# base-base.net
KiCad netlist of a schematic drawn in EAGLE
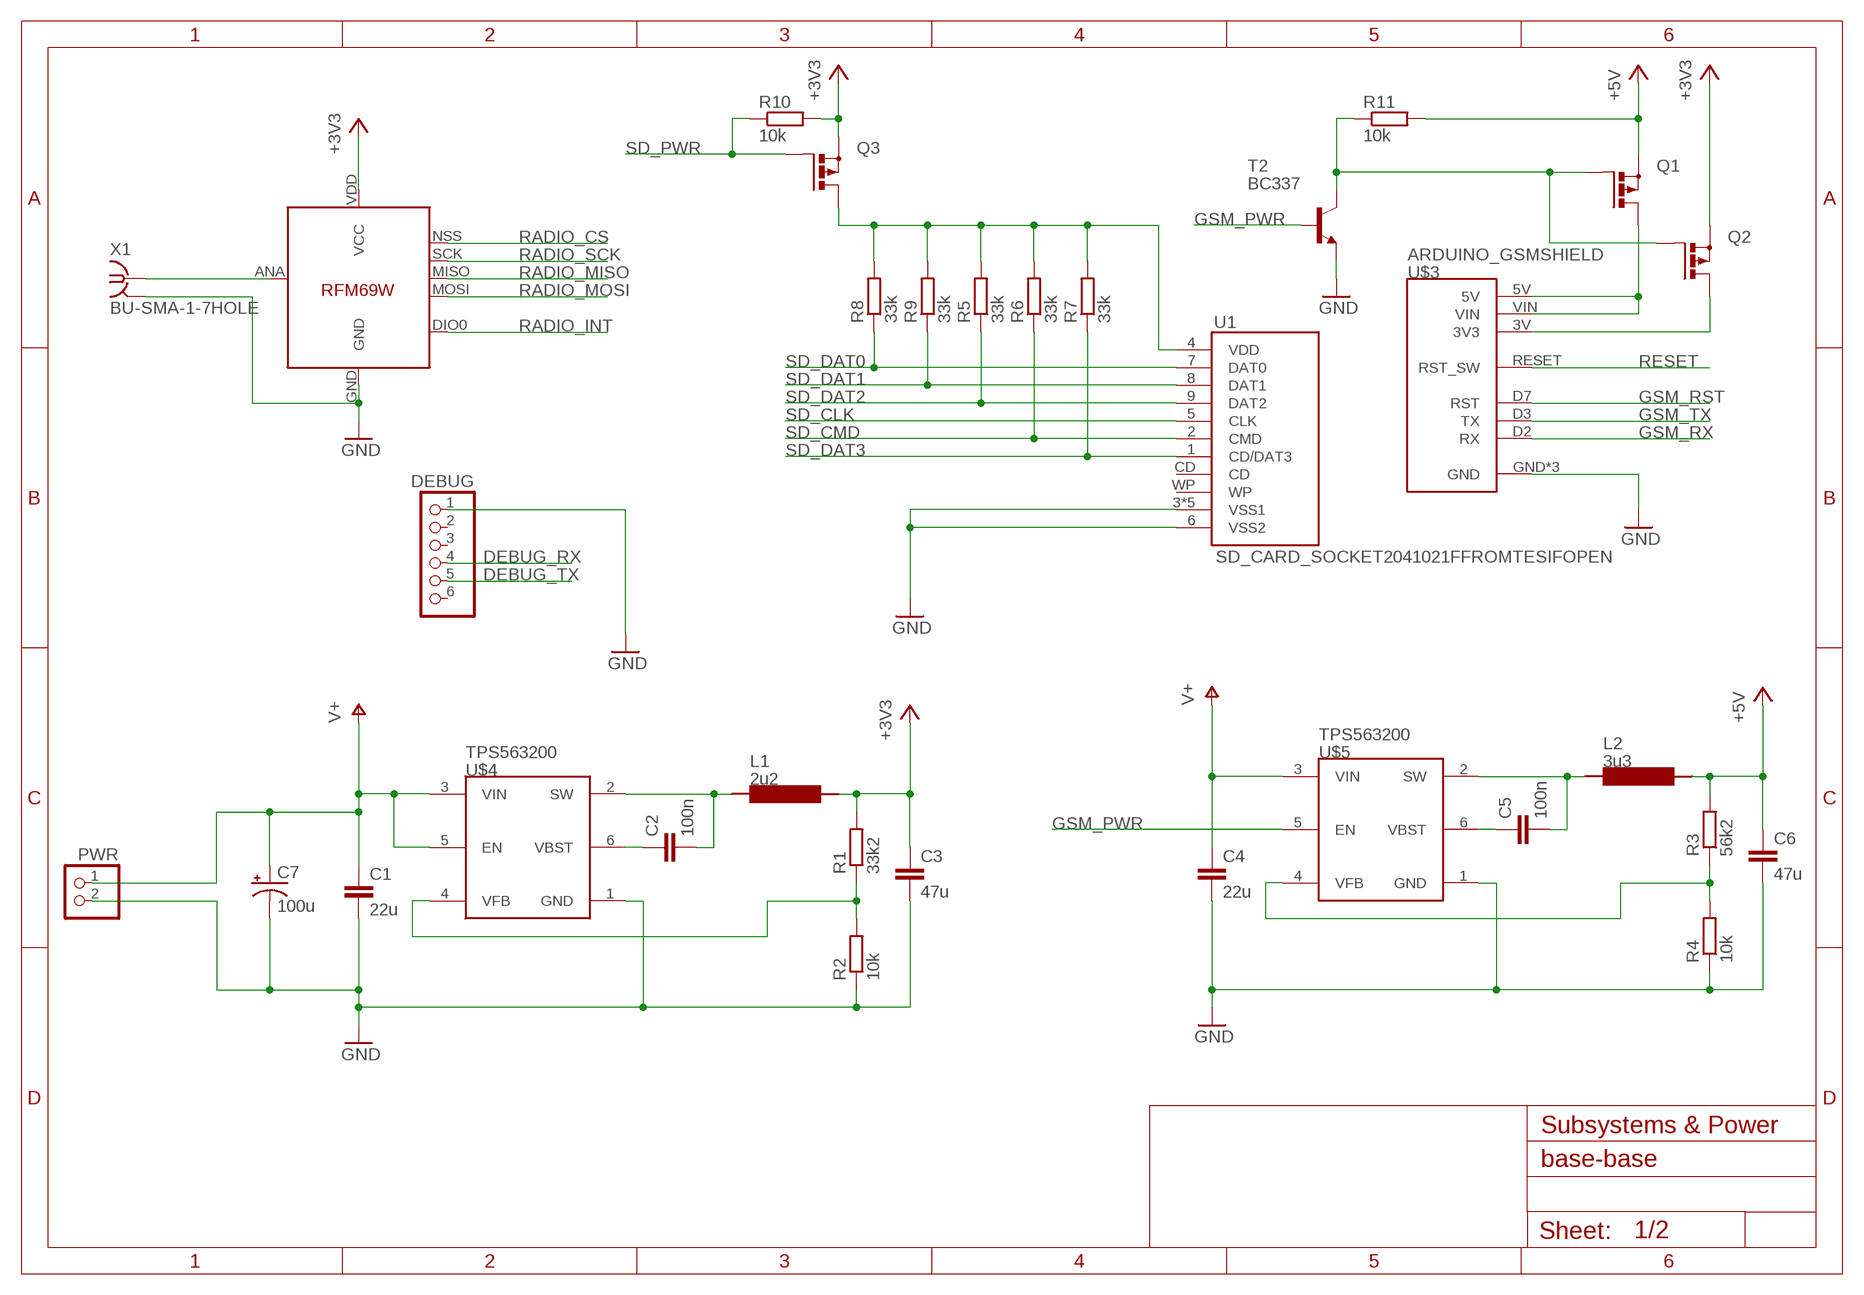
[diagram p0: schematic, sheet 1]
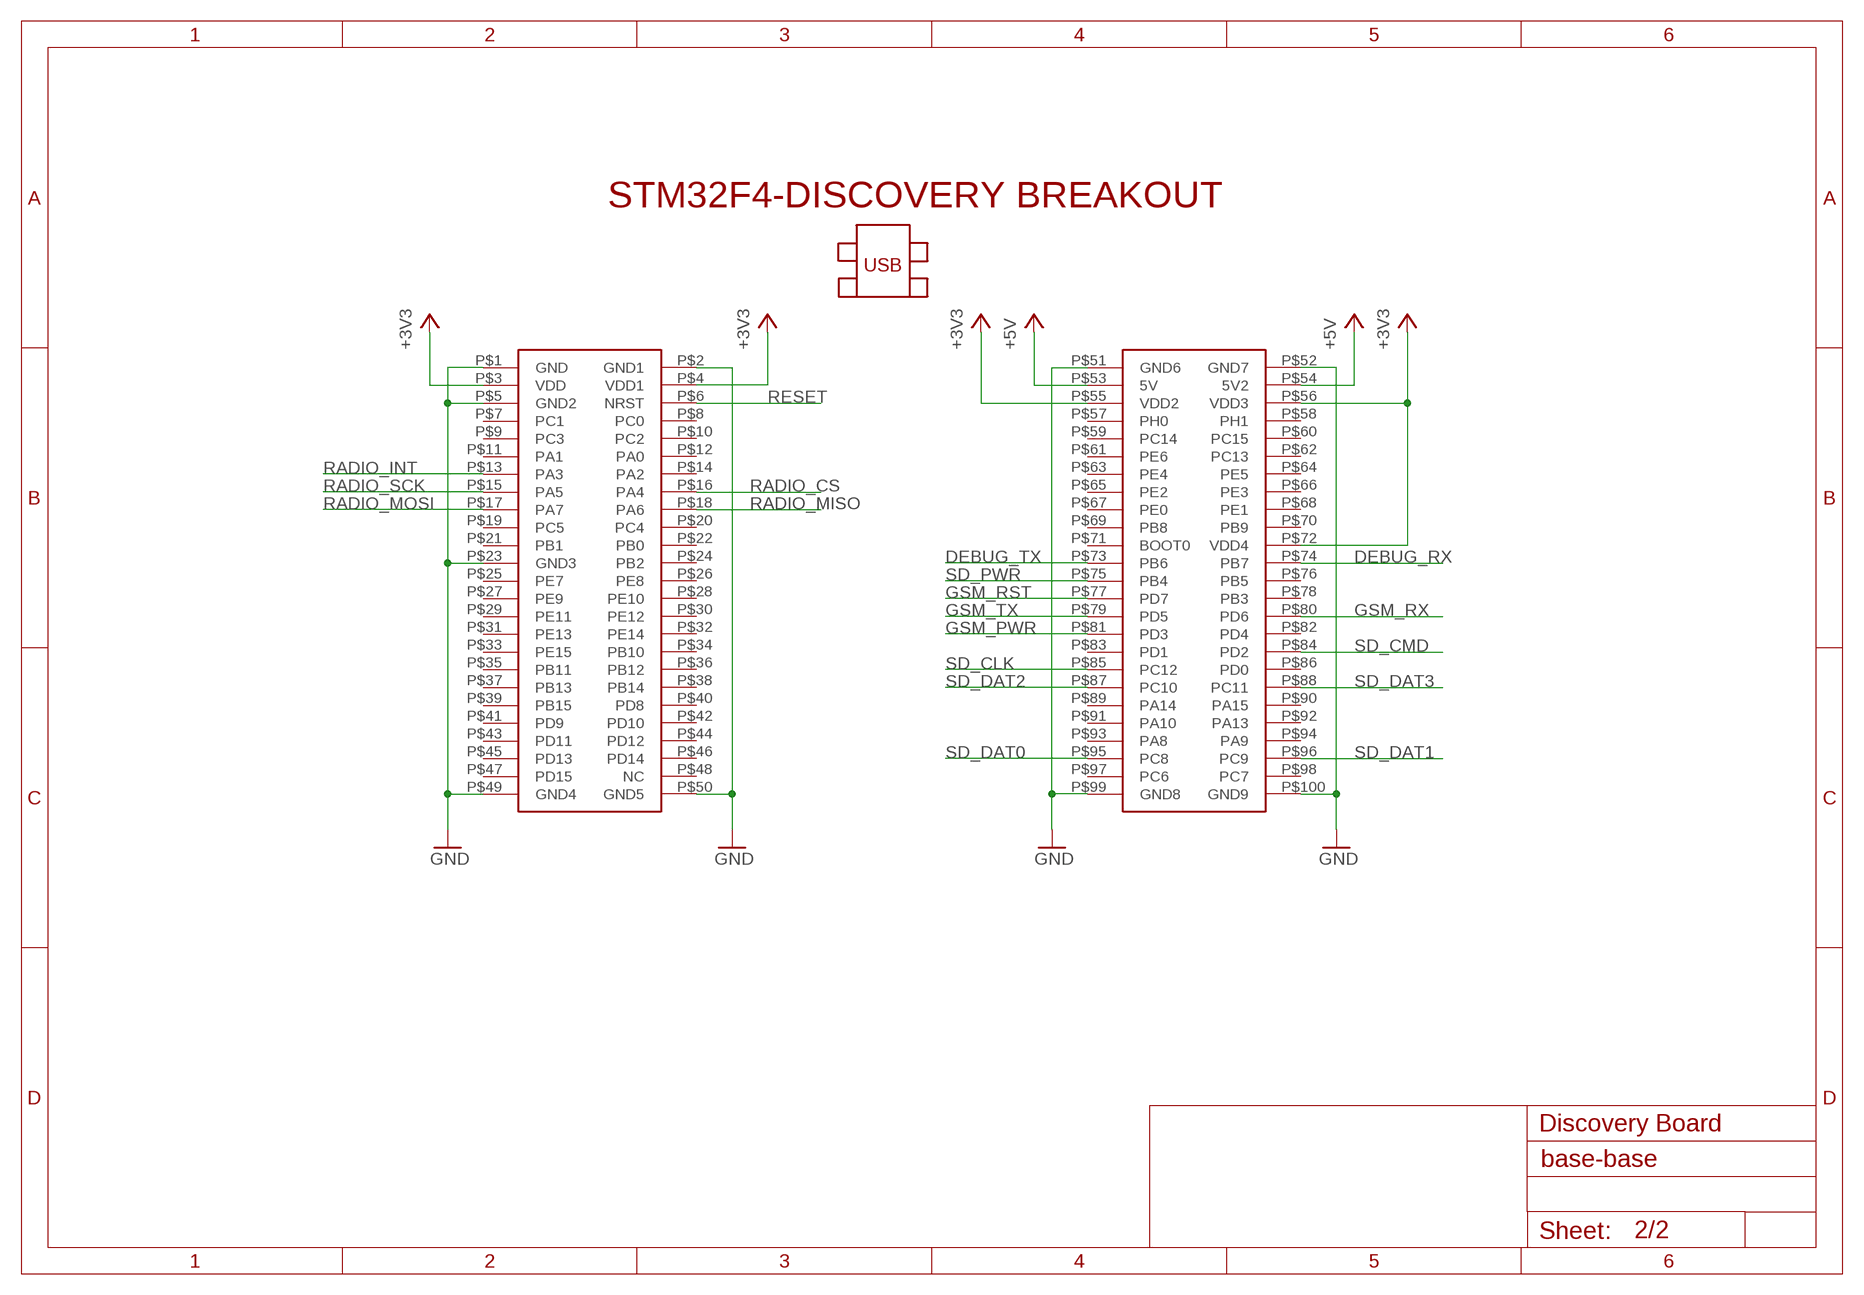
[diagram p1: schematic, sheet 2]

(export (version "E")
  (design (tool "Eeschema 10.0.6"))
  (components
    (comp (ref "U$1")
      (value "STM32F4-DISCOVERY")
      (footprint "eagle-import:STM32F4-DISCOVERY")
      (libsource (lib "eagle-import") (part "STM32F4-DISCOVERY"))
    )
    (comp (ref "C1")
      (value "22u")
      (footprint "eagle-import:1206")
      (libsource (lib "eagle-import") (part "CAP1206"))
    )
    (comp (ref "C2")
      (value "100n")
      (footprint "eagle-import:CAP-PTH-SMALL")
      (libsource (lib "eagle-import") (part "CAPPTH"))
    )
    (comp (ref "C3")
      (value "47u")
      (footprint "eagle-import:1206")
      (libsource (lib "eagle-import") (part "CAP1206"))
    )
    (comp (ref "C4")
      (value "22u")
      (footprint "eagle-import:1206")
      (libsource (lib "eagle-import") (part "CAP1206"))
    )
    (comp (ref "C5")
      (value "100n")
      (footprint "eagle-import:CAP-PTH-SMALL")
      (libsource (lib "eagle-import") (part "CAPPTH"))
    )
    (comp (ref "C6")
      (value "47u")
      (footprint "eagle-import:1206")
      (libsource (lib "eagle-import") (part "CAP1206"))
    )
    (comp (ref "C7")
      (value "100u")
      (footprint "eagle-import:CPOL-RADIAL-10UF-25V")
      (libsource (lib "eagle-import") (part "CAP_POLPTH2"))
    )
    (comp (ref "DEBUG")
      (value "PINHD-1X6")
      (footprint "eagle-import:1X06")
      (libsource (lib "eagle-import") (part "PINHD-1X6"))
    )
    (comp (ref "L1")
      (value "2u2")
      (footprint "eagle-import:SRR7032")
      (libsource (lib "eagle-import") (part "SRR7032"))
    )
    (comp (ref "L2")
      (value "3u3")
      (footprint "eagle-import:SRR7032")
      (libsource (lib "eagle-import") (part "SRR7032"))
    )
    (comp (ref "PWR")
      (value "PINHD-1X2")
      (footprint "eagle-import:1X02")
      (libsource (lib "eagle-import") (part "PINHD-1X2"))
    )
    (comp (ref "Q1")
      (value "PMOSFET_PTO220BH")
      (footprint "eagle-import:TO220BH")
      (libsource (lib "eagle-import") (part "PMOSFET_PTO220BH"))
    )
    (comp (ref "Q2")
      (value "PMOSFET_PTO220BH")
      (footprint "eagle-import:TO220BH")
      (libsource (lib "eagle-import") (part "PMOSFET_PTO220BH"))
    )
    (comp (ref "Q3")
      (value "PMOSFET_PTO220BH")
      (footprint "eagle-import:TO220BH")
      (libsource (lib "eagle-import") (part "PMOSFET_PTO220BH"))
    )
    (comp (ref "R1")
      (value "33k2")
      (footprint "eagle-import:0204_7")
      (libsource (lib "eagle-import") (part "R-EU_0204/7"))
    )
    (comp (ref "R2")
      (value "10k")
      (footprint "eagle-import:0204_7")
      (libsource (lib "eagle-import") (part "R-EU_0204/7"))
    )
    (comp (ref "R3")
      (value "56k2")
      (footprint "eagle-import:0204_7")
      (libsource (lib "eagle-import") (part "R-EU_0204/7"))
    )
    (comp (ref "R4")
      (value "10k")
      (footprint "eagle-import:0204_7")
      (libsource (lib "eagle-import") (part "R-EU_0204/7"))
    )
    (comp (ref "R5")
      (value "33k")
      (footprint "eagle-import:0204_7")
      (libsource (lib "eagle-import") (part "R-EU_0204/7"))
    )
    (comp (ref "R6")
      (value "33k")
      (footprint "eagle-import:0204_7")
      (libsource (lib "eagle-import") (part "R-EU_0204/7"))
    )
    (comp (ref "R7")
      (value "33k")
      (footprint "eagle-import:0204_7")
      (libsource (lib "eagle-import") (part "R-EU_0204/7"))
    )
    (comp (ref "R8")
      (value "33k")
      (footprint "eagle-import:0204_7")
      (libsource (lib "eagle-import") (part "R-EU_0204/7"))
    )
    (comp (ref "R9")
      (value "33k")
      (footprint "eagle-import:0204_7")
      (libsource (lib "eagle-import") (part "R-EU_0204/7"))
    )
    (comp (ref "R10")
      (value "10k")
      (footprint "eagle-import:0204_7")
      (libsource (lib "eagle-import") (part "R-EU_0204/7"))
    )
    (comp (ref "R11")
      (value "10k")
      (footprint "eagle-import:0204_7")
      (libsource (lib "eagle-import") (part "R-EU_0204/7"))
    )
    (comp (ref "T2")
      (value "BC337")
      (footprint "eagle-import:TO92")
      (libsource (lib "eagle-import") (part "BC337"))
    )
    (comp (ref "U$2")
      (value "RFM69")
      (footprint "eagle-import:RFM69W-MINPADS")
      (libsource (lib "eagle-import") (part "RFM69"))
    )
    (comp (ref "U$3")
      (value "ARDUINO_GSMSHIELD")
      (footprint "eagle-import:ARDUINO-NOHOLE")
      (libsource (lib "eagle-import") (part "ARDUINO_GSMSHIELD"))
    )
    (comp (ref "U$4")
      (value "TPS563200")
      (footprint "eagle-import:DDC0006A")
      (libsource (lib "eagle-import") (part "TPS563200"))
    )
    (comp (ref "U$5")
      (value "TPS563200")
      (footprint "eagle-import:DDC0006A")
      (libsource (lib "eagle-import") (part "TPS563200"))
    )
    (comp (ref "U1")
      (value "SD_CARD_SOCKET2041021FFROMTESIFOPEN")
      (footprint "eagle-import:SDCARD_2041021-3")
      (libsource (lib "eagle-import") (part "SD_CARD_SOCKET2041021FFROMTESIFOPEN"))
    )
    (comp (ref "X1")
      (value "BU-SMA-1-7HOLE")
      (footprint "eagle-import:SMA_1-7HOLES")
      (libsource (lib "eagle-import") (part "BU-SMA-1-7HOLE"))
    )
  )
  (nets
    (net (code "1") (name "+3V3") (class "Default")
      (node (ref "C3") (pin "1") (pinfunction "1_1") (pintype "passive"))
      (node (ref "L1") (pin "2") (pinfunction "2_2") (pintype "passive"))
      (node (ref "Q2") (pin "S") (pinfunction "S_S") (pintype "passive"))
      (node (ref "Q3") (pin "S") (pinfunction "S_S") (pintype "passive"))
      (node (ref "R1") (pin "2") (pinfunction "2_2") (pintype "passive"))
      (node (ref "R10") (pin "2") (pinfunction "2_2") (pintype "passive"))
      (node (ref "U$1") (pin "P$3") (pinfunction "VDD_P$3") (pintype "bidirectional"))
      (node (ref "U$1") (pin "P$4") (pinfunction "VDD1_P$4") (pintype "bidirectional"))
      (node (ref "U$1") (pin "P$55") (pinfunction "VDD2_P$55") (pintype "bidirectional"))
      (node (ref "U$1") (pin "P$56") (pinfunction "VDD3_P$56") (pintype "bidirectional"))
      (node (ref "U$1") (pin "P$72") (pinfunction "VDD4_P$72") (pintype "bidirectional"))
      (node (ref "U$2") (pin "VDD") (pinfunction "VCC_VDD") (pintype "power_in"))
    )
    (net (code "2") (name "+5V") (class "Default")
      (node (ref "C6") (pin "1") (pinfunction "1_1") (pintype "passive"))
      (node (ref "L2") (pin "2") (pinfunction "2_2") (pintype "passive"))
      (node (ref "Q1") (pin "S") (pinfunction "S_S") (pintype "passive"))
      (node (ref "R11") (pin "2") (pinfunction "2_2") (pintype "passive"))
      (node (ref "R3") (pin "2") (pinfunction "2_2") (pintype "passive"))
      (node (ref "U$1") (pin "P$53") (pinfunction "5V_P$53") (pintype "bidirectional"))
      (node (ref "U$1") (pin "P$54") (pinfunction "5V2_P$54") (pintype "bidirectional"))
    )
    (net (code "3") (name "DEBUG_RX") (class "Default")
      (node (ref "DEBUG") (pin "4") (pinfunction "4_4") (pintype "passive"))
      (node (ref "U$1") (pin "P$74") (pinfunction "PB7_P$74") (pintype "bidirectional"))
    )
    (net (code "4") (name "DEBUG_TX") (class "Default")
      (node (ref "DEBUG") (pin "5") (pinfunction "5_5") (pintype "passive"))
      (node (ref "U$1") (pin "P$73") (pinfunction "PB6_P$73") (pintype "bidirectional"))
    )
    (net (code "5") (name "GND") (class "Default")
      (node (ref "C1") (pin "2") (pinfunction "2_2") (pintype "passive"))
      (node (ref "C3") (pin "2") (pinfunction "2_2") (pintype "passive"))
      (node (ref "C4") (pin "2") (pinfunction "2_2") (pintype "passive"))
      (node (ref "C6") (pin "2") (pinfunction "2_2") (pintype "passive"))
      (node (ref "C7") (pin "2") (pinfunction "-_2") (pintype "passive"))
      (node (ref "DEBUG") (pin "1") (pinfunction "1_1") (pintype "passive"))
      (node (ref "PWR") (pin "2") (pinfunction "2_2") (pintype "passive"))
      (node (ref "R2") (pin "1") (pinfunction "1_1") (pintype "passive"))
      (node (ref "R4") (pin "1") (pinfunction "1_1") (pintype "passive"))
      (node (ref "T2") (pin "1") (pinfunction "E_1") (pintype "passive"))
      (node (ref "U$1") (pin "P$1") (pinfunction "GND_P$1") (pintype "bidirectional"))
      (node (ref "U$1") (pin "P$100") (pinfunction "GND9_P$100") (pintype "bidirectional"))
      (node (ref "U$1") (pin "P$2") (pinfunction "GND1_P$2") (pintype "bidirectional"))
      (node (ref "U$1") (pin "P$23") (pinfunction "GND3_P$23") (pintype "bidirectional"))
      (node (ref "U$1") (pin "P$49") (pinfunction "GND4_P$49") (pintype "bidirectional"))
      (node (ref "U$1") (pin "P$5") (pinfunction "GND2_P$5") (pintype "bidirectional"))
      (node (ref "U$1") (pin "P$50") (pinfunction "GND5_P$50") (pintype "bidirectional"))
      (node (ref "U$1") (pin "P$51") (pinfunction "GND6_P$51") (pintype "bidirectional"))
      (node (ref "U$1") (pin "P$52") (pinfunction "GND7_P$52") (pintype "bidirectional"))
      (node (ref "U$1") (pin "P$99") (pinfunction "GND8_P$99") (pintype "bidirectional"))
      (node (ref "U$2") (pin "GND") (pinfunction "GND_GND") (pintype "power_in"))
      (node (ref "U$3") (pin "GND") (pinfunction "GND_GND") (pintype "bidirectional"))
      (node (ref "U$3") (pin "GND1") (pinfunction "GND_GND1") (pintype "bidirectional"))
      (node (ref "U$3") (pin "GND2") (pinfunction "GND_GND2") (pintype "bidirectional"))
      (node (ref "U$4") (pin "1") (pinfunction "GND_1") (pintype "bidirectional"))
      (node (ref "U$5") (pin "1") (pinfunction "GND_1") (pintype "bidirectional"))
      (node (ref "U1") (pin "3") (pinfunction "VSS1_3") (pintype "power_in"))
      (node (ref "U1") (pin "6") (pinfunction "VSS2_6") (pintype "power_in"))
      (node (ref "U1") (pin "SH1") (pinfunction "VSS1_SH1") (pintype "power_in"))
      (node (ref "U1") (pin "SH2") (pinfunction "VSS1_SH2") (pintype "power_in"))
      (node (ref "U1") (pin "SH3") (pinfunction "VSS1_SH3") (pintype "power_in"))
      (node (ref "U1") (pin "SH4") (pinfunction "VSS1_SH4") (pintype "power_in"))
      (node (ref "X1") (pin "2") (pinfunction "2_2") (pintype "passive"))
      (node (ref "X1") (pin "3") (pinfunction "2_3") (pintype "passive"))
      (node (ref "X1") (pin "4") (pinfunction "2_4") (pintype "passive"))
      (node (ref "X1") (pin "5") (pinfunction "2_5") (pintype "passive"))
    )
    (net (code "6") (name "GSM_PWR") (class "Default")
      (node (ref "T2") (pin "2") (pinfunction "B_2") (pintype "passive"))
      (node (ref "U$1") (pin "P$81") (pinfunction "PD3_P$81") (pintype "bidirectional"))
      (node (ref "U$5") (pin "5") (pinfunction "EN_5") (pintype "bidirectional"))
    )
    (net (code "7") (name "GSM_RST") (class "Default")
      (node (ref "U$1") (pin "P$77") (pinfunction "PD7_P$77") (pintype "bidirectional"))
      (node (ref "U$3") (pin "D7") (pinfunction "RST_D7") (pintype "bidirectional"))
    )
    (net (code "8") (name "GSM_RX") (class "Default")
      (node (ref "U$1") (pin "P$80") (pinfunction "PD6_P$80") (pintype "bidirectional"))
      (node (ref "U$3") (pin "D2") (pinfunction "RX_D2") (pintype "bidirectional"))
    )
    (net (code "9") (name "GSM_TX") (class "Default")
      (node (ref "U$1") (pin "P$79") (pinfunction "PD5_P$79") (pintype "bidirectional"))
      (node (ref "U$3") (pin "D3") (pinfunction "TX_D3") (pintype "bidirectional"))
    )
    (net (code "10") (name "Net-(Q1-PadD)") (class "Default")
      (node (ref "Q1") (pin "D") (pinfunction "D_D") (pintype "passive"))
      (node (ref "U$3") (pin "5V") (pinfunction "5V_5V") (pintype "bidirectional"))
      (node (ref "U$3") (pin "VIN") (pinfunction "VIN_VIN") (pintype "bidirectional"))
    )
    (net (code "11") (name "Net-(T2-C)") (class "Default")
      (node (ref "Q1") (pin "G") (pinfunction "G_G") (pintype "passive"))
      (node (ref "Q2") (pin "G") (pinfunction "G_G") (pintype "passive"))
      (node (ref "R11") (pin "1") (pinfunction "1_1") (pintype "passive"))
      (node (ref "T2") (pin "3") (pinfunction "C_3") (pintype "passive"))
    )
    (net (code "12") (name "Net-(U$2-ANT)") (class "Default")
      (node (ref "U$2") (pin "ANA") (pinfunction "ANT_ANA") (pintype "passive"))
      (node (ref "X1") (pin "1") (pinfunction "1_1") (pintype "passive"))
    )
    (net (code "13") (name "Net-(U$3-3V3)") (class "Default")
      (node (ref "Q2") (pin "D") (pinfunction "D_D") (pintype "passive"))
      (node (ref "U$3") (pin "3V") (pinfunction "3V3_3V") (pintype "bidirectional"))
    )
    (net (code "14") (name "Net-(U$4-SW)") (class "Default")
      (node (ref "C2") (pin "2") (pinfunction "2_2") (pintype "passive"))
      (node (ref "L1") (pin "1") (pinfunction "1_1") (pintype "passive"))
      (node (ref "U$4") (pin "2") (pinfunction "SW_2") (pintype "bidirectional"))
    )
    (net (code "15") (name "Net-(U$4-VBST)") (class "Default")
      (node (ref "C2") (pin "1") (pinfunction "1_1") (pintype "passive"))
      (node (ref "U$4") (pin "6") (pinfunction "VBST_6") (pintype "bidirectional"))
    )
    (net (code "16") (name "Net-(U$4-VFB)") (class "Default")
      (node (ref "R1") (pin "1") (pinfunction "1_1") (pintype "passive"))
      (node (ref "R2") (pin "2") (pinfunction "2_2") (pintype "passive"))
      (node (ref "U$4") (pin "4") (pinfunction "VFB_4") (pintype "bidirectional"))
    )
    (net (code "17") (name "Net-(U$5-SW)") (class "Default")
      (node (ref "C5") (pin "2") (pinfunction "2_2") (pintype "passive"))
      (node (ref "L2") (pin "1") (pinfunction "1_1") (pintype "passive"))
      (node (ref "U$5") (pin "2") (pinfunction "SW_2") (pintype "bidirectional"))
    )
    (net (code "18") (name "Net-(U$5-VBST)") (class "Default")
      (node (ref "C5") (pin "1") (pinfunction "1_1") (pintype "passive"))
      (node (ref "U$5") (pin "6") (pinfunction "VBST_6") (pintype "bidirectional"))
    )
    (net (code "19") (name "Net-(U$5-VFB)") (class "Default")
      (node (ref "R3") (pin "1") (pinfunction "1_1") (pintype "passive"))
      (node (ref "R4") (pin "2") (pinfunction "2_2") (pintype "passive"))
      (node (ref "U$5") (pin "4") (pinfunction "VFB_4") (pintype "bidirectional"))
    )
    (net (code "20") (name "Net-(U1-VDD)") (class "Default")
      (node (ref "Q3") (pin "D") (pinfunction "D_D") (pintype "passive"))
      (node (ref "R5") (pin "2") (pinfunction "2_2") (pintype "passive"))
      (node (ref "R6") (pin "2") (pinfunction "2_2") (pintype "passive"))
      (node (ref "R7") (pin "2") (pinfunction "2_2") (pintype "passive"))
      (node (ref "R8") (pin "2") (pinfunction "2_2") (pintype "passive"))
      (node (ref "R9") (pin "2") (pinfunction "2_2") (pintype "passive"))
      (node (ref "U1") (pin "4") (pinfunction "VDD_4") (pintype "power_in"))
    )
    (net (code "21") (name "RADIO_CS") (class "Default")
      (node (ref "U$1") (pin "P$16") (pinfunction "PA4_P$16") (pintype "bidirectional"))
      (node (ref "U$2") (pin "NSS") (pinfunction "SEL_NSS") (pintype "input"))
    )
    (net (code "22") (name "RADIO_INT") (class "Default")
      (node (ref "U$1") (pin "P$13") (pinfunction "PA3_P$13") (pintype "bidirectional"))
      (node (ref "U$2") (pin "DIO0") (pinfunction "DIO0_DIO0") (pintype "open_collector"))
    )
    (net (code "23") (name "RADIO_MISO") (class "Default")
      (node (ref "U$1") (pin "P$18") (pinfunction "PA6_P$18") (pintype "bidirectional"))
      (node (ref "U$2") (pin "MISO") (pinfunction "MISO_MISO") (pintype "input"))
    )
    (net (code "24") (name "RADIO_MOSI") (class "Default")
      (node (ref "U$1") (pin "P$17") (pinfunction "PA7_P$17") (pintype "bidirectional"))
      (node (ref "U$2") (pin "MOSI") (pinfunction "MOSI_MOSI") (pintype "output"))
    )
    (net (code "25") (name "RADIO_SCK") (class "Default")
      (node (ref "U$1") (pin "P$15") (pinfunction "PA5_P$15") (pintype "bidirectional"))
      (node (ref "U$2") (pin "SCK") (pinfunction "SCK_SCK") (pintype "input"))
    )
    (net (code "26") (name "RESET") (class "Default")
      (node (ref "U$1") (pin "P$6") (pinfunction "NRST_P$6") (pintype "bidirectional"))
      (node (ref "U$3") (pin "RESET") (pinfunction "RST_SW_RESET") (pintype "bidirectional"))
    )
    (net (code "27") (name "SD_CLK") (class "Default")
      (node (ref "U$1") (pin "P$85") (pinfunction "PC12_P$85") (pintype "bidirectional"))
      (node (ref "U1") (pin "5") (pinfunction "CLK_5") (pintype "bidirectional"))
    )
    (net (code "28") (name "SD_CMD") (class "Default")
      (node (ref "R6") (pin "1") (pinfunction "1_1") (pintype "passive"))
      (node (ref "U$1") (pin "P$84") (pinfunction "PD2_P$84") (pintype "bidirectional"))
      (node (ref "U1") (pin "2") (pinfunction "CMD_2") (pintype "bidirectional"))
    )
    (net (code "29") (name "SD_DAT0") (class "Default")
      (node (ref "R8") (pin "1") (pinfunction "1_1") (pintype "passive"))
      (node (ref "U$1") (pin "P$95") (pinfunction "PC8_P$95") (pintype "bidirectional"))
      (node (ref "U1") (pin "7") (pinfunction "DAT0_7") (pintype "bidirectional"))
    )
    (net (code "30") (name "SD_DAT1") (class "Default")
      (node (ref "R9") (pin "1") (pinfunction "1_1") (pintype "passive"))
      (node (ref "U$1") (pin "P$96") (pinfunction "PC9_P$96") (pintype "bidirectional"))
      (node (ref "U1") (pin "8") (pinfunction "DAT1_8") (pintype "bidirectional"))
    )
    (net (code "31") (name "SD_DAT2") (class "Default")
      (node (ref "R5") (pin "1") (pinfunction "1_1") (pintype "passive"))
      (node (ref "U$1") (pin "P$87") (pinfunction "PC10_P$87") (pintype "bidirectional"))
      (node (ref "U1") (pin "9") (pinfunction "DAT2_9") (pintype "bidirectional"))
    )
    (net (code "32") (name "SD_DAT3") (class "Default")
      (node (ref "R7") (pin "1") (pinfunction "1_1") (pintype "passive"))
      (node (ref "U$1") (pin "P$88") (pinfunction "PC11_P$88") (pintype "bidirectional"))
      (node (ref "U1") (pin "1") (pinfunction "CD/DAT3_1") (pintype "bidirectional"))
    )
    (net (code "33") (name "SD_PWR") (class "Default")
      (node (ref "Q3") (pin "G") (pinfunction "G_G") (pintype "passive"))
      (node (ref "R10") (pin "1") (pinfunction "1_1") (pintype "passive"))
      (node (ref "U$1") (pin "P$75") (pinfunction "PB4_P$75") (pintype "bidirectional"))
    )
    (net (code "34") (name "V+") (class "Default")
      (node (ref "C1") (pin "1") (pinfunction "1_1") (pintype "passive"))
      (node (ref "C4") (pin "1") (pinfunction "1_1") (pintype "passive"))
      (node (ref "C7") (pin "1") (pinfunction "+_1") (pintype "passive"))
      (node (ref "PWR") (pin "1") (pinfunction "1_1") (pintype "passive"))
      (node (ref "U$4") (pin "3") (pinfunction "VIN_3") (pintype "bidirectional"))
      (node (ref "U$4") (pin "5") (pinfunction "EN_5") (pintype "bidirectional"))
      (node (ref "U$5") (pin "3") (pinfunction "VIN_3") (pintype "bidirectional"))
    )
    (net (code "35") (name "unconnected-(DEBUG-Pad2)") (class "Default")
      (node (ref "DEBUG") (pin "2") (pinfunction "2_2") (pintype "passive"))
    )
    (net (code "36") (name "unconnected-(DEBUG-Pad3)") (class "Default")
      (node (ref "DEBUG") (pin "3") (pinfunction "3_3") (pintype "passive"))
    )
    (net (code "37") (name "unconnected-(DEBUG-Pad6)") (class "Default")
      (node (ref "DEBUG") (pin "6") (pinfunction "6_6") (pintype "passive"))
    )
    (net (code "38") (name "unconnected-(U$1-BOOT0-PadP$71)") (class "Default")
      (node (ref "U$1") (pin "P$71") (pinfunction "BOOT0_P$71") (pintype "bidirectional"))
    )
    (net (code "39") (name "unconnected-(U$1-NC-PadP$48)") (class "Default")
      (node (ref "U$1") (pin "P$48") (pinfunction "NC_P$48") (pintype "bidirectional"))
    )
    (net (code "40") (name "unconnected-(U$1-PA0-PadP$12)") (class "Default")
      (node (ref "U$1") (pin "P$12") (pinfunction "PA0_P$12") (pintype "bidirectional"))
    )
    (net (code "41") (name "unconnected-(U$1-PA1-PadP$11)") (class "Default")
      (node (ref "U$1") (pin "P$11") (pinfunction "PA1_P$11") (pintype "bidirectional"))
    )
    (net (code "42") (name "unconnected-(U$1-PA2-PadP$14)") (class "Default")
      (node (ref "U$1") (pin "P$14") (pinfunction "PA2_P$14") (pintype "bidirectional"))
    )
    (net (code "43") (name "unconnected-(U$1-PA8-PadP$93)") (class "Default")
      (node (ref "U$1") (pin "P$93") (pinfunction "PA8_P$93") (pintype "bidirectional"))
    )
    (net (code "44") (name "unconnected-(U$1-PA9-PadP$94)") (class "Default")
      (node (ref "U$1") (pin "P$94") (pinfunction "PA9_P$94") (pintype "bidirectional"))
    )
    (net (code "45") (name "unconnected-(U$1-PA10-PadP$91)") (class "Default")
      (node (ref "U$1") (pin "P$91") (pinfunction "PA10_P$91") (pintype "bidirectional"))
    )
    (net (code "46") (name "unconnected-(U$1-PA13-PadP$92)") (class "Default")
      (node (ref "U$1") (pin "P$92") (pinfunction "PA13_P$92") (pintype "bidirectional"))
    )
    (net (code "47") (name "unconnected-(U$1-PA14-PadP$89)") (class "Default")
      (node (ref "U$1") (pin "P$89") (pinfunction "PA14_P$89") (pintype "bidirectional"))
    )
    (net (code "48") (name "unconnected-(U$1-PA15-PadP$90)") (class "Default")
      (node (ref "U$1") (pin "P$90") (pinfunction "PA15_P$90") (pintype "bidirectional"))
    )
    (net (code "49") (name "unconnected-(U$1-PB0-PadP$22)") (class "Default")
      (node (ref "U$1") (pin "P$22") (pinfunction "PB0_P$22") (pintype "bidirectional"))
    )
    (net (code "50") (name "unconnected-(U$1-PB1-PadP$21)") (class "Default")
      (node (ref "U$1") (pin "P$21") (pinfunction "PB1_P$21") (pintype "bidirectional"))
    )
    (net (code "51") (name "unconnected-(U$1-PB2-PadP$24)") (class "Default")
      (node (ref "U$1") (pin "P$24") (pinfunction "PB2_P$24") (pintype "bidirectional"))
    )
    (net (code "52") (name "unconnected-(U$1-PB3-PadP$78)") (class "Default")
      (node (ref "U$1") (pin "P$78") (pinfunction "PB3_P$78") (pintype "bidirectional"))
    )
    (net (code "53") (name "unconnected-(U$1-PB5-PadP$76)") (class "Default")
      (node (ref "U$1") (pin "P$76") (pinfunction "PB5_P$76") (pintype "bidirectional"))
    )
    (net (code "54") (name "unconnected-(U$1-PB8-PadP$69)") (class "Default")
      (node (ref "U$1") (pin "P$69") (pinfunction "PB8_P$69") (pintype "bidirectional"))
    )
    (net (code "55") (name "unconnected-(U$1-PB9-PadP$70)") (class "Default")
      (node (ref "U$1") (pin "P$70") (pinfunction "PB9_P$70") (pintype "bidirectional"))
    )
    (net (code "56") (name "unconnected-(U$1-PB10-PadP$34)") (class "Default")
      (node (ref "U$1") (pin "P$34") (pinfunction "PB10_P$34") (pintype "bidirectional"))
    )
    (net (code "57") (name "unconnected-(U$1-PB11-PadP$35)") (class "Default")
      (node (ref "U$1") (pin "P$35") (pinfunction "PB11_P$35") (pintype "bidirectional"))
    )
    (net (code "58") (name "unconnected-(U$1-PB12-PadP$36)") (class "Default")
      (node (ref "U$1") (pin "P$36") (pinfunction "PB12_P$36") (pintype "bidirectional"))
    )
    (net (code "59") (name "unconnected-(U$1-PB13-PadP$37)") (class "Default")
      (node (ref "U$1") (pin "P$37") (pinfunction "PB13_P$37") (pintype "bidirectional"))
    )
    (net (code "60") (name "unconnected-(U$1-PB14-PadP$38)") (class "Default")
      (node (ref "U$1") (pin "P$38") (pinfunction "PB14_P$38") (pintype "bidirectional"))
    )
    (net (code "61") (name "unconnected-(U$1-PB15-PadP$39)") (class "Default")
      (node (ref "U$1") (pin "P$39") (pinfunction "PB15_P$39") (pintype "bidirectional"))
    )
    (net (code "62") (name "unconnected-(U$1-PC0-PadP$8)") (class "Default")
      (node (ref "U$1") (pin "P$8") (pinfunction "PC0_P$8") (pintype "bidirectional"))
    )
    (net (code "63") (name "unconnected-(U$1-PC1-PadP$7)") (class "Default")
      (node (ref "U$1") (pin "P$7") (pinfunction "PC1_P$7") (pintype "bidirectional"))
    )
    (net (code "64") (name "unconnected-(U$1-PC2-PadP$10)") (class "Default")
      (node (ref "U$1") (pin "P$10") (pinfunction "PC2_P$10") (pintype "bidirectional"))
    )
    (net (code "65") (name "unconnected-(U$1-PC3-PadP$9)") (class "Default")
      (node (ref "U$1") (pin "P$9") (pinfunction "PC3_P$9") (pintype "bidirectional"))
    )
    (net (code "66") (name "unconnected-(U$1-PC4-PadP$20)") (class "Default")
      (node (ref "U$1") (pin "P$20") (pinfunction "PC4_P$20") (pintype "bidirectional"))
    )
    (net (code "67") (name "unconnected-(U$1-PC5-PadP$19)") (class "Default")
      (node (ref "U$1") (pin "P$19") (pinfunction "PC5_P$19") (pintype "bidirectional"))
    )
    (net (code "68") (name "unconnected-(U$1-PC6-PadP$97)") (class "Default")
      (node (ref "U$1") (pin "P$97") (pinfunction "PC6_P$97") (pintype "bidirectional"))
    )
    (net (code "69") (name "unconnected-(U$1-PC7-PadP$98)") (class "Default")
      (node (ref "U$1") (pin "P$98") (pinfunction "PC7_P$98") (pintype "bidirectional"))
    )
    (net (code "70") (name "unconnected-(U$1-PC13-PadP$62)") (class "Default")
      (node (ref "U$1") (pin "P$62") (pinfunction "PC13_P$62") (pintype "bidirectional"))
    )
    (net (code "71") (name "unconnected-(U$1-PC14-PadP$59)") (class "Default")
      (node (ref "U$1") (pin "P$59") (pinfunction "PC14_P$59") (pintype "bidirectional"))
    )
    (net (code "72") (name "unconnected-(U$1-PC15-PadP$60)") (class "Default")
      (node (ref "U$1") (pin "P$60") (pinfunction "PC15_P$60") (pintype "bidirectional"))
    )
    (net (code "73") (name "unconnected-(U$1-PD0-PadP$86)") (class "Default")
      (node (ref "U$1") (pin "P$86") (pinfunction "PD0_P$86") (pintype "bidirectional"))
    )
    (net (code "74") (name "unconnected-(U$1-PD1-PadP$83)") (class "Default")
      (node (ref "U$1") (pin "P$83") (pinfunction "PD1_P$83") (pintype "bidirectional"))
    )
    (net (code "75") (name "unconnected-(U$1-PD4-PadP$82)") (class "Default")
      (node (ref "U$1") (pin "P$82") (pinfunction "PD4_P$82") (pintype "bidirectional"))
    )
    (net (code "76") (name "unconnected-(U$1-PD8-PadP$40)") (class "Default")
      (node (ref "U$1") (pin "P$40") (pinfunction "PD8_P$40") (pintype "bidirectional"))
    )
    (net (code "77") (name "unconnected-(U$1-PD9-PadP$41)") (class "Default")
      (node (ref "U$1") (pin "P$41") (pinfunction "PD9_P$41") (pintype "bidirectional"))
    )
    (net (code "78") (name "unconnected-(U$1-PD10-PadP$42)") (class "Default")
      (node (ref "U$1") (pin "P$42") (pinfunction "PD10_P$42") (pintype "bidirectional"))
    )
    (net (code "79") (name "unconnected-(U$1-PD11-PadP$43)") (class "Default")
      (node (ref "U$1") (pin "P$43") (pinfunction "PD11_P$43") (pintype "bidirectional"))
    )
    (net (code "80") (name "unconnected-(U$1-PD12-PadP$44)") (class "Default")
      (node (ref "U$1") (pin "P$44") (pinfunction "PD12_P$44") (pintype "bidirectional"))
    )
    (net (code "81") (name "unconnected-(U$1-PD13-PadP$45)") (class "Default")
      (node (ref "U$1") (pin "P$45") (pinfunction "PD13_P$45") (pintype "bidirectional"))
    )
    (net (code "82") (name "unconnected-(U$1-PD14-PadP$46)") (class "Default")
      (node (ref "U$1") (pin "P$46") (pinfunction "PD14_P$46") (pintype "bidirectional"))
    )
    (net (code "83") (name "unconnected-(U$1-PD15-PadP$47)") (class "Default")
      (node (ref "U$1") (pin "P$47") (pinfunction "PD15_P$47") (pintype "bidirectional"))
    )
    (net (code "84") (name "unconnected-(U$1-PE0-PadP$67)") (class "Default")
      (node (ref "U$1") (pin "P$67") (pinfunction "PE0_P$67") (pintype "bidirectional"))
    )
    (net (code "85") (name "unconnected-(U$1-PE1-PadP$68)") (class "Default")
      (node (ref "U$1") (pin "P$68") (pinfunction "PE1_P$68") (pintype "bidirectional"))
    )
    (net (code "86") (name "unconnected-(U$1-PE2-PadP$65)") (class "Default")
      (node (ref "U$1") (pin "P$65") (pinfunction "PE2_P$65") (pintype "bidirectional"))
    )
    (net (code "87") (name "unconnected-(U$1-PE3-PadP$66)") (class "Default")
      (node (ref "U$1") (pin "P$66") (pinfunction "PE3_P$66") (pintype "bidirectional"))
    )
    (net (code "88") (name "unconnected-(U$1-PE4-PadP$63)") (class "Default")
      (node (ref "U$1") (pin "P$63") (pinfunction "PE4_P$63") (pintype "bidirectional"))
    )
    (net (code "89") (name "unconnected-(U$1-PE5-PadP$64)") (class "Default")
      (node (ref "U$1") (pin "P$64") (pinfunction "PE5_P$64") (pintype "bidirectional"))
    )
    (net (code "90") (name "unconnected-(U$1-PE6-PadP$61)") (class "Default")
      (node (ref "U$1") (pin "P$61") (pinfunction "PE6_P$61") (pintype "bidirectional"))
    )
    (net (code "91") (name "unconnected-(U$1-PE7-PadP$25)") (class "Default")
      (node (ref "U$1") (pin "P$25") (pinfunction "PE7_P$25") (pintype "bidirectional"))
    )
    (net (code "92") (name "unconnected-(U$1-PE8-PadP$26)") (class "Default")
      (node (ref "U$1") (pin "P$26") (pinfunction "PE8_P$26") (pintype "bidirectional"))
    )
    (net (code "93") (name "unconnected-(U$1-PE9-PadP$27)") (class "Default")
      (node (ref "U$1") (pin "P$27") (pinfunction "PE9_P$27") (pintype "bidirectional"))
    )
    (net (code "94") (name "unconnected-(U$1-PE10-PadP$28)") (class "Default")
      (node (ref "U$1") (pin "P$28") (pinfunction "PE10_P$28") (pintype "bidirectional"))
    )
    (net (code "95") (name "unconnected-(U$1-PE11-PadP$29)") (class "Default")
      (node (ref "U$1") (pin "P$29") (pinfunction "PE11_P$29") (pintype "bidirectional"))
    )
    (net (code "96") (name "unconnected-(U$1-PE12-PadP$30)") (class "Default")
      (node (ref "U$1") (pin "P$30") (pinfunction "PE12_P$30") (pintype "bidirectional"))
    )
    (net (code "97") (name "unconnected-(U$1-PE13-PadP$31)") (class "Default")
      (node (ref "U$1") (pin "P$31") (pinfunction "PE13_P$31") (pintype "bidirectional"))
    )
    (net (code "98") (name "unconnected-(U$1-PE14-PadP$32)") (class "Default")
      (node (ref "U$1") (pin "P$32") (pinfunction "PE14_P$32") (pintype "bidirectional"))
    )
    (net (code "99") (name "unconnected-(U$1-PE15-PadP$33)") (class "Default")
      (node (ref "U$1") (pin "P$33") (pinfunction "PE15_P$33") (pintype "bidirectional"))
    )
    (net (code "100") (name "unconnected-(U$1-PH0-PadP$57)") (class "Default")
      (node (ref "U$1") (pin "P$57") (pinfunction "PH0_P$57") (pintype "bidirectional"))
    )
    (net (code "101") (name "unconnected-(U$1-PH1-PadP$58)") (class "Default")
      (node (ref "U$1") (pin "P$58") (pinfunction "PH1_P$58") (pintype "bidirectional"))
    )
    (net (code "102") (name "unconnected-(U1-PadCD)") (class "Default")
      (node (ref "U1") (pin "CD") (pinfunction "CD_CD") (pintype "bidirectional"))
    )
    (net (code "103") (name "unconnected-(U1-PadWP)") (class "Default")
      (node (ref "U1") (pin "WP") (pinfunction "WP_WP") (pintype "bidirectional"))
    )
  )
)
